# pmu_2.net
KiCad netlist of a schematic drawn in Altium Designer
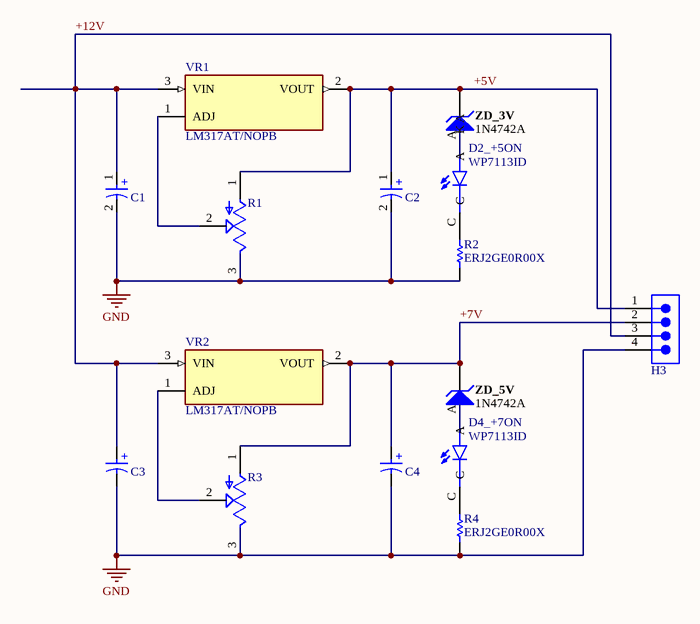
[diagram p0: pmu_2.SchDoc]

(export (version "E")
  (design (tool "Eeschema 10.0.6"))
  (components
    (comp (ref "C1")
      (value "2.2µF")
      (footprint "pmu:WCAP-ATG5_D5H11")
      (description "WCAP-ATG5 Aluminum Electrolytic Capacitor, Radial, THT, D5 x H11mm, 2.2µF, 50V")
      (fields
        (field (name "MANUFACTURER PART NUMBER") "860020672006")
        (field (name "MANUFACTURER") "Wurth Elektronik")
      )
      (libsource (lib "") (part "860020672006_1"))
    )
    (comp (ref "C2")
      (value "1.1uF")
      (footprint "pmu:WCAP-ATG5_D5H11")
      (description "WCAP-ATG5 Aluminum Electrolytic Capacitor, Radial, THT, D5 x H11mm, 2.2µF, 50V")
      (fields
        (field (name "MANUFACTURER PART NUMBER") "860020672006")
        (field (name "MANUFACTURER") "Wurth Elektronik")
      )
      (libsource (lib "") (part "860020672006_1"))
    )
    (comp (ref "C3")
      (value "2.2µF")
      (footprint "WCAP-ATG5_D5H11")
      (description "WCAP-ATG5 Aluminum Electrolytic Capacitor, Radial, THT, D5 x H11mm, 2.2µF, 50V")
      (fields
        (field (name "MANUFACTURER PART NUMBER") "860020672006")
        (field (name "MANUFACTURER") "Wurth Elektronik")
      )
      (libsource (lib "1ufcap-Altium_WCAP-ATG5_rev22d") (part "860020672006"))
    )
    (comp (ref "C4")
      (value "1.1uF")
      (footprint "pmu:WCAP-ATG5_D5H11")
      (description "WCAP-ATG5 Aluminum Electrolytic Capacitor, Radial, THT, D5 x H11mm, 2.2µF, 50V")
      (fields
        (field (name "MANUFACTURER PART NUMBER") "860020672006")
        (field (name "MANUFACTURER") "Wurth Elektronik")
      )
      (libsource (lib "1ufcap-Altium_WCAP-ATG5_rev22d") (part "860020672006"))
    )
    (comp (ref "D2_+5ON")
      (value "WP7113ID")
      (footprint "pmu:LED_WP7113ID")
      (description "Red 617nm LED Indication - Discrete 2V Radial")
      (fields (field (name "MF") "Kingbright"))
      (libsource (lib "leds-WP7113ID") (part "WP7113ID"))
    )
    (comp (ref "D4_+7ON")
      (value "WP7113ID")
      (footprint "pmu:LED_WP7113ID")
      (description "Red 617nm LED Indication - Discrete 2V Radial")
      (fields (field (name "MF") "Kingbright"))
      (libsource (lib "leds-WP7113ID") (part "WP7113ID"))
    )
    (comp (ref "H3")
      (value "61300411121")
      (footprint "61300411121")
      (description "WR-PHD Pin Header, THT, Vertical, pitch 2.54mm, 1 Row, 4P")
      (fields (field (name "MANUFACTURER") "Wurth Elektronik"))
      (libsource (lib "pmu") (part "61300411121"))
    )
    (comp (ref "R1")
      (value "~")
      (footprint "TRIM_3362P-1-103LF")
      (description "10 kOhms 0.5W, 1/2W PC Pins Through Hole Trimmer Potentiometer Cermet 1 Turn Top Adjustment")
      (fields (field (name "DIGI-KEY_PART_NUMBER") "3362P-103LF-ND") (field (name "MF") "Bourns"))
      (libsource (lib "*") (part "3362P-1-103LF"))
    )
    (comp (ref "R2")
      (value "ERJ2GE0R00X")
      (footprint "RESC1005X40X25LL05T05")
      (description "Chip Resistor, 0 Ohm, 0.1 W, -55 to 155 degC, 0402 (1005 Metric), RoHS, Tape and Reel")
      (fields (field (name "MANUFACTURER") "Panasonic") (field (name "TOLERANCE") "5%"))
      (libsource (lib "Altium Content Vault") (part "RES-2"))
    )
    (comp (ref "R3")
      (value "~")
      (footprint "TRIM_3362P-1-103LF")
      (description "10 kOhms 0.5W, 1/2W PC Pins Through Hole Trimmer Potentiometer Cermet 1 Turn Top Adjustment")
      (fields (field (name "DIGI-KEY_PART_NUMBER") "3362P-103LF-ND") (field (name "MF") "Bourns"))
      (libsource (lib "*") (part "3362P-1-103LF"))
    )
    (comp (ref "R4")
      (value "ERJ2GE0R00X")
      (footprint "RESC1005X40X25LL05T05")
      (description "Chip Resistor, 0 Ohm, 0.1 W, -55 to 155 degC, 0402 (1005 Metric), RoHS, Tape and Reel")
      (fields (field (name "MANUFACTURER") "Panasonic") (field (name "TOLERANCE") "5%"))
      (libsource (lib "Altium Content Vault") (part "RES-2"))
    )
    (comp (ref "VR1")
      (value "LM317AT/NOPB")
      (footprint "pmu:TO254P1054X470X1955-3")
      (libsource (lib "vreg-LM317AT_NOPB") (part "LM317AT/NOPB"))
    )
    (comp (ref "VR2")
      (value "LM317AT/NOPB")
      (footprint "pmu:TO254P1054X470X1955-3")
      (libsource (lib "vreg-LM317AT_NOPB") (part "LM317AT/NOPB"))
    )
    (comp (ref "ZD_3V")
      (value "1N4742A")
      (footprint "FAIR-DO-41-2_V")
      (description "Zener Diode, 12V, 1W, 5%, -65 to 200 degC, 2-Pin DO-41, Body 2.72 x 5.2 mm, RoHS")
      (fields (field (name "TOLERANCE") "5%") (field (name "MANUFACTURER") "Fairchild Semiconductor"))
      (libsource (lib "Altium Content Vault") (part "FAIR-DZEN-A1K2-2"))
    )
    (comp (ref "ZD_5V")
      (value "1N4742A")
      (footprint "FAIR-DO-41-2_V")
      (description "Zener Diode, 12V, 1W, 5%, -65 to 200 degC, 2-Pin DO-41, Body 2.72 x 5.2 mm, RoHS")
      (fields (field (name "TOLERANCE") "5%") (field (name "MANUFACTURER") "Fairchild Semiconductor"))
      (libsource (lib "") (part "FAIR-DZEN-A1K2-2_1"))
    )
  )
  (nets
    (net (code "1") (name "/+5V") (class "Default")
      (node (ref "C2") (pin "1") (pinfunction "P_1") (pintype "passive"))
      (node (ref "H3") (pin "1") (pinfunction "1_1") (pintype "passive"))
      (node (ref "R1") (pin "1") (pinfunction "CCW_1") (pintype "passive"))
      (node (ref "VR1") (pin "2") (pinfunction "VOUT_2") (pintype "output"))
      (node (ref "ZD_3V") (pin "2") (pinfunction "K_2") (pintype "passive"))
    )
    (net (code "2") (name "/+7V") (class "Default")
      (node (ref "C4") (pin "1") (pinfunction "P_1") (pintype "passive"))
      (node (ref "H3") (pin "2") (pinfunction "2_2") (pintype "passive"))
      (node (ref "R3") (pin "1") (pinfunction "CCW_1") (pintype "passive"))
      (node (ref "VR2") (pin "2") (pinfunction "VOUT_2") (pintype "output"))
      (node (ref "ZD_5V") (pin "2") (pinfunction "K_2") (pintype "passive"))
    )
    (net (code "3") (name "/+12V") (class "Default")
      (node (ref "C1") (pin "1") (pinfunction "P_1") (pintype "passive"))
      (node (ref "C3") (pin "1") (pinfunction "P_1") (pintype "passive"))
      (node (ref "H3") (pin "3") (pinfunction "3_3") (pintype "passive"))
      (node (ref "VR1") (pin "3") (pinfunction "VIN_3") (pintype "input"))
      (node (ref "VR2") (pin "3") (pinfunction "VIN_3") (pintype "input"))
    )
    (net (code "4") (name "GND") (class "Default")
      (node (ref "C1") (pin "2") (pinfunction "N_2") (pintype "passive"))
      (node (ref "C2") (pin "2") (pinfunction "N_2") (pintype "passive"))
      (node (ref "C3") (pin "2") (pinfunction "N_2") (pintype "passive"))
      (node (ref "C4") (pin "2") (pinfunction "N_2") (pintype "passive"))
      (node (ref "H3") (pin "4") (pinfunction "4_4") (pintype "passive"))
      (node (ref "R1") (pin "3") (pinfunction "CW_3") (pintype "passive"))
      (node (ref "R2") (pin "1") (pinfunction "1_1") (pintype "passive"))
      (node (ref "R3") (pin "3") (pinfunction "CW_3") (pintype "passive"))
      (node (ref "R4") (pin "1") (pinfunction "1_1") (pintype "passive"))
    )
    (net (code "5") (name "Net-(D2_+5ON-PadC)") (class "Default")
      (node (ref "D2_+5ON") (pin "C") (pinfunction "C_C") (pintype "passive"))
      (node (ref "R2") (pin "2") (pinfunction "2_2") (pintype "passive"))
    )
    (net (code "6") (name "Net-(D4_+7ON-PadC)") (class "Default")
      (node (ref "D4_+7ON") (pin "C") (pinfunction "C_C") (pintype "passive"))
      (node (ref "R4") (pin "2") (pinfunction "2_2") (pintype "passive"))
    )
    (net (code "7") (name "Net-(R1-WIPER)") (class "Default")
      (node (ref "R1") (pin "2") (pinfunction "WIPER_2") (pintype "passive"))
      (node (ref "VR1") (pin "1") (pinfunction "ADJ_1") (pintype "passive"))
    )
    (net (code "8") (name "Net-(R3-WIPER)") (class "Default")
      (node (ref "R3") (pin "2") (pinfunction "WIPER_2") (pintype "passive"))
      (node (ref "VR2") (pin "1") (pinfunction "ADJ_1") (pintype "passive"))
    )
    (net (code "9") (name "Net-(ZD_3V-A)") (class "Default")
      (node (ref "D2_+5ON") (pin "A") (pinfunction "A_A") (pintype "passive"))
      (node (ref "ZD_3V") (pin "1") (pinfunction "A_1") (pintype "passive"))
    )
    (net (code "10") (name "Net-(ZD_5V-A)") (class "Default")
      (node (ref "D4_+7ON") (pin "A") (pinfunction "A_A") (pintype "passive"))
      (node (ref "ZD_5V") (pin "1") (pinfunction "A_1") (pintype "passive"))
    )
  )
)
